# EMG-bi-single.net
KiCad netlist of a schematic drawn in EAGLE
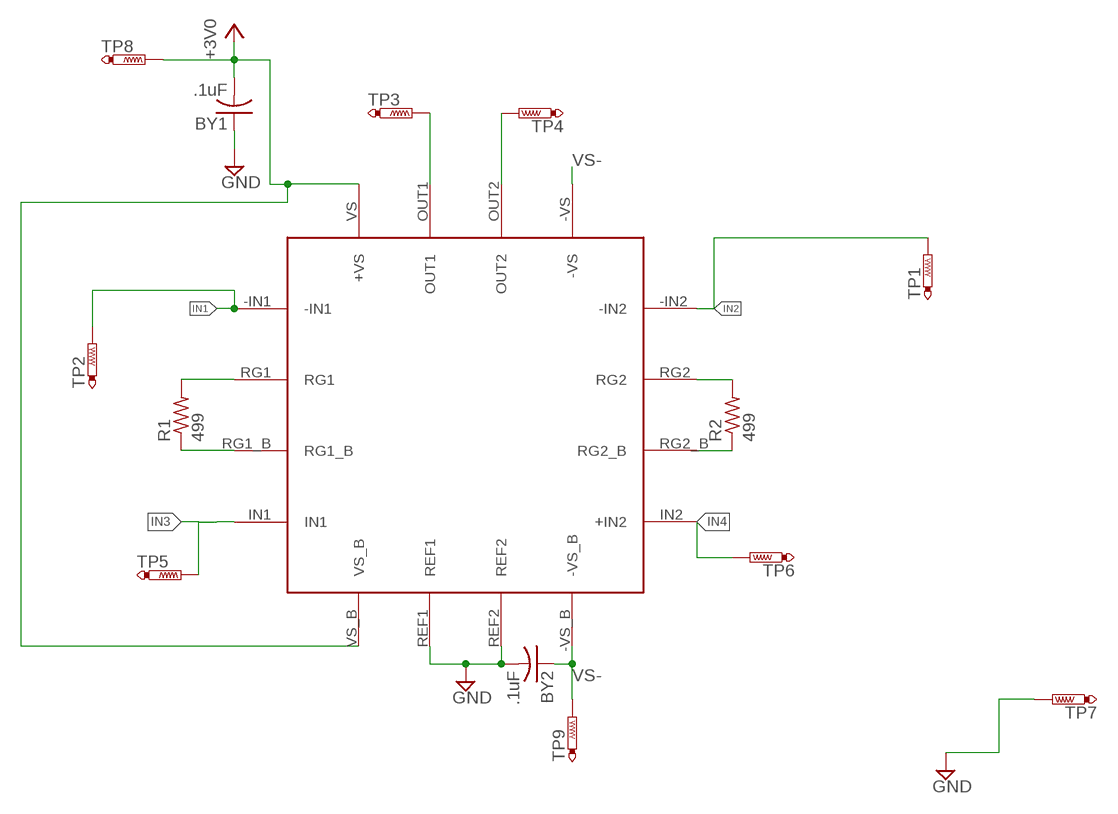
[diagram p0: schematic, sheet 1]

(export (version "E")
  (design (tool "Eeschema 10.0.6"))
  (components
    (comp (ref "BY1")
      (value ".1uF")
      (footprint "eagle-import:C0805")
      (libsource (lib "eagle-import") (part "C-USC0805"))
    )
    (comp (ref "BY2")
      (value ".1uF")
      (footprint "eagle-import:C0805")
      (libsource (lib "eagle-import") (part "C-USC0805"))
    )
    (comp (ref "R1")
      (value "499")
      (footprint "eagle-import:R0805")
      (libsource (lib "eagle-import") (part "R-US_R0805"))
    )
    (comp (ref "R2")
      (value "499")
      (footprint "eagle-import:R0805")
      (libsource (lib "eagle-import") (part "R-US_R0805"))
    )
    (comp (ref "TP1")
      (value "PTR1TP20SQ")
      (footprint "eagle-import:TP20SQ")
      (libsource (lib "eagle-import") (part "PTR1TP20SQ"))
    )
    (comp (ref "TP2")
      (value "PTR1TP20SQ")
      (footprint "eagle-import:TP20SQ")
      (libsource (lib "eagle-import") (part "PTR1TP20SQ"))
    )
    (comp (ref "TP3")
      (value "PTR1TP20SQ")
      (footprint "eagle-import:TP20SQ")
      (libsource (lib "eagle-import") (part "PTR1TP20SQ"))
    )
    (comp (ref "TP4")
      (value "PTR1TP20SQ")
      (footprint "eagle-import:TP20SQ")
      (libsource (lib "eagle-import") (part "PTR1TP20SQ"))
    )
    (comp (ref "TP5")
      (value "PTR1TP20SQ")
      (footprint "eagle-import:TP20SQ")
      (libsource (lib "eagle-import") (part "PTR1TP20SQ"))
    )
    (comp (ref "TP6")
      (value "PTR1TP20SQ")
      (footprint "eagle-import:TP20SQ")
      (libsource (lib "eagle-import") (part "PTR1TP20SQ"))
    )
    (comp (ref "TP7")
      (value "PTR1TP20SQ")
      (footprint "eagle-import:TP20SQ")
      (libsource (lib "eagle-import") (part "PTR1TP20SQ"))
    )
    (comp (ref "TP8")
      (value "PTR1TP20SQ")
      (footprint "eagle-import:TP20SQ")
      (libsource (lib "eagle-import") (part "PTR1TP20SQ"))
    )
    (comp (ref "TP9")
      (value "PTR1TP20SQ")
      (footprint "eagle-import:TP20SQ")
      (libsource (lib "eagle-import") (part "PTR1TP20SQ"))
    )
    (comp (ref "U$9")
      (value "AD8222")
      (footprint "eagle-import:QFN-16")
      (libsource (lib "eagle-import") (part "AD8222"))
    )
  )
  (nets
    (net (code "1") (name "+3V0") (class "Default")
      (node (ref "BY1") (pin "2") (pinfunction "2_2") (pintype "passive"))
      (node (ref "TP8") (pin "TP") (pinfunction "TP_TP") (pintype "input"))
      (node (ref "U$9") (pin "VS") (pinfunction "+VS_VS") (pintype "bidirectional"))
      (node (ref "U$9") (pin "VS_B") (pinfunction "VS_B_VS_B") (pintype "bidirectional"))
    )
    (net (code "2") (name "/VS-") (class "Default")
      (node (ref "BY2") (pin "1") (pinfunction "1_1") (pintype "passive"))
      (node (ref "TP9") (pin "TP") (pinfunction "TP_TP") (pintype "input"))
      (node (ref "U$9") (pin "-VS") (pinfunction "-VS_-VS") (pintype "bidirectional"))
      (node (ref "U$9") (pin "-VS_B") (pinfunction "-VS_B_-VS_B") (pintype "bidirectional"))
    )
    (net (code "3") (name "GND") (class "Default")
      (node (ref "BY1") (pin "1") (pinfunction "1_1") (pintype "passive"))
      (node (ref "BY2") (pin "2") (pinfunction "2_2") (pintype "passive"))
      (node (ref "TP7") (pin "TP") (pinfunction "TP_TP") (pintype "input"))
      (node (ref "U$9") (pin "REF1") (pinfunction "REF1_REF1") (pintype "bidirectional"))
      (node (ref "U$9") (pin "REF2") (pinfunction "REF2_REF2") (pintype "bidirectional"))
    )
    (net (code "4") (name "IN1") (class "Default")
      (node (ref "TP2") (pin "TP") (pinfunction "TP_TP") (pintype "input"))
      (node (ref "U$9") (pin "-IN1") (pinfunction "-IN1_-IN1") (pintype "bidirectional"))
    )
    (net (code "5") (name "IN2") (class "Default")
      (node (ref "TP1") (pin "TP") (pinfunction "TP_TP") (pintype "input"))
      (node (ref "U$9") (pin "-IN2") (pinfunction "-IN2_-IN2") (pintype "bidirectional"))
    )
    (net (code "6") (name "IN3") (class "Default")
      (node (ref "TP5") (pin "TP") (pinfunction "TP_TP") (pintype "input"))
      (node (ref "U$9") (pin "IN1") (pinfunction "IN1_IN1") (pintype "bidirectional"))
    )
    (net (code "7") (name "IN4") (class "Default")
      (node (ref "TP6") (pin "TP") (pinfunction "TP_TP") (pintype "input"))
      (node (ref "U$9") (pin "IN2") (pinfunction "+IN2_IN2") (pintype "bidirectional"))
    )
    (net (code "8") (name "Net-(R1-Pad1)") (class "Default")
      (node (ref "R1") (pin "1") (pinfunction "1_1") (pintype "passive"))
      (node (ref "U$9") (pin "RG1_B") (pinfunction "RG1_B_RG1_B") (pintype "bidirectional"))
    )
    (net (code "9") (name "Net-(R1-Pad2)") (class "Default")
      (node (ref "R1") (pin "2") (pinfunction "2_2") (pintype "passive"))
      (node (ref "U$9") (pin "RG1") (pinfunction "RG1_RG1") (pintype "bidirectional"))
    )
    (net (code "10") (name "Net-(R2-Pad1)") (class "Default")
      (node (ref "R2") (pin "1") (pinfunction "1_1") (pintype "passive"))
      (node (ref "U$9") (pin "RG2_B") (pinfunction "RG2_B_RG2_B") (pintype "bidirectional"))
    )
    (net (code "11") (name "Net-(R2-Pad2)") (class "Default")
      (node (ref "R2") (pin "2") (pinfunction "2_2") (pintype "passive"))
      (node (ref "U$9") (pin "RG2") (pinfunction "RG2_RG2") (pintype "bidirectional"))
    )
    (net (code "12") (name "Net-(TP3-PadTP)") (class "Default")
      (node (ref "TP3") (pin "TP") (pinfunction "TP_TP") (pintype "input"))
      (node (ref "U$9") (pin "OUT1") (pinfunction "OUT1_OUT1") (pintype "bidirectional"))
    )
    (net (code "13") (name "Net-(TP4-PadTP)") (class "Default")
      (node (ref "TP4") (pin "TP") (pinfunction "TP_TP") (pintype "input"))
      (node (ref "U$9") (pin "OUT2") (pinfunction "OUT2_OUT2") (pintype "bidirectional"))
    )
  )
)
